# trill-ring.net
KiCad netlist of a schematic drawn in EAGLE
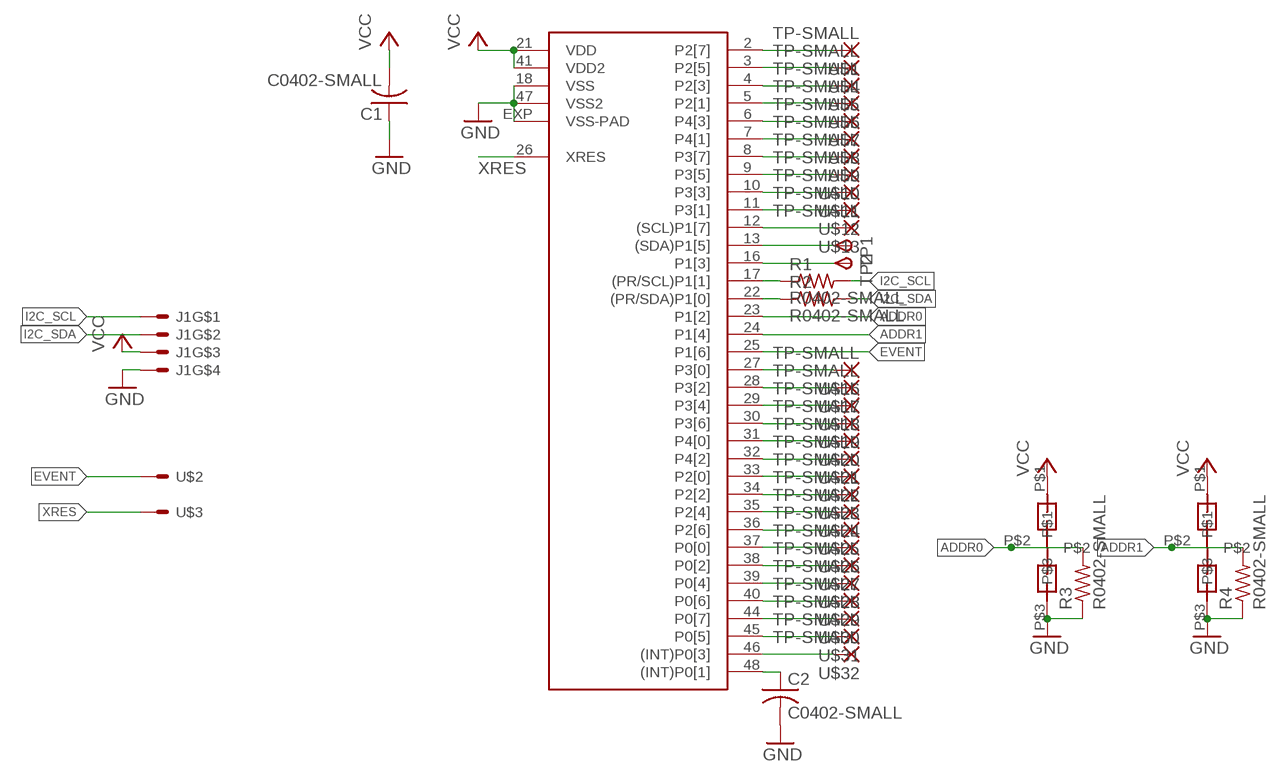
[diagram p0: schematic, sheet 1]

(export (version "E")
  (design (tool "Eeschema 10.0.6"))
  (components
    (comp (ref "C1")
      (value "C0402-SMALL")
      (footprint "eagle-import:C0402-SMALL")
      (libsource (lib "eagle-import") (part "C0402-SMALL"))
    )
    (comp (ref "C2")
      (value "C0402-SMALL")
      (footprint "eagle-import:C0402-SMALL")
      (libsource (lib "eagle-import") (part "C0402-SMALL"))
    )
    (comp (ref "IC1")
      (value "CY8C206X6A")
      (footprint "eagle-import:QFN48-LEADS")
      (libsource (lib "eagle-import") (part "CY8C206X6A"))
    )
    (comp (ref "J1")
      (value "GROVE-SMT")
      (footprint "eagle-import:JST-PH-4-SMT")
      (libsource (lib "eagle-import") (part "GROVE-SMT"))
    )
    (comp (ref "R1")
      (value "R0402-SMALL")
      (footprint "eagle-import:C0402-SMALL")
      (libsource (lib "eagle-import") (part "R0402-SMALL"))
    )
    (comp (ref "R2")
      (value "R0402-SMALL")
      (footprint "eagle-import:C0402-SMALL")
      (libsource (lib "eagle-import") (part "R0402-SMALL"))
    )
    (comp (ref "R3")
      (value "R0402-SMALL")
      (footprint "eagle-import:C0402-SMALL")
      (libsource (lib "eagle-import") (part "R0402-SMALL"))
    )
    (comp (ref "R4")
      (value "R0402-SMALL")
      (footprint "eagle-import:C0402-SMALL")
      (libsource (lib "eagle-import") (part "R0402-SMALL"))
    )
    (comp (ref "TP1")
      (value "TPSTP20R")
      (footprint "eagle-import:TP20R")
      (libsource (lib "eagle-import") (part "TPSTP20R"))
    )
    (comp (ref "TP2")
      (value "TPSTP20R")
      (footprint "eagle-import:TP20R")
      (libsource (lib "eagle-import") (part "TPSTP20R"))
    )
    (comp (ref "U$1")
      (value "TP-SMALL")
      (footprint "eagle-import:TESTPAD-SMALL")
      (libsource (lib "eagle-import") (part "TP-SMALL"))
    )
    (comp (ref "U$2")
      (value "JST-SMT-EXTRAPAD")
      (footprint "eagle-import:JST-SMT-EXTRAPAD")
      (libsource (lib "eagle-import") (part "JST-SMT-EXTRAPAD"))
    )
    (comp (ref "U$3")
      (value "JST-SMT-EXTRAPAD")
      (footprint "eagle-import:JST-SMT-EXTRAPAD")
      (libsource (lib "eagle-import") (part "JST-SMT-EXTRAPAD"))
    )
    (comp (ref "U$4")
      (value "TP-SMALL")
      (footprint "eagle-import:TESTPAD-SMALL")
      (libsource (lib "eagle-import") (part "TP-SMALL"))
    )
    (comp (ref "U$5")
      (value "TP-SMALL")
      (footprint "eagle-import:TESTPAD-SMALL")
      (libsource (lib "eagle-import") (part "TP-SMALL"))
    )
    (comp (ref "U$6")
      (value "TP-SMALL")
      (footprint "eagle-import:TESTPAD-SMALL")
      (libsource (lib "eagle-import") (part "TP-SMALL"))
    )
    (comp (ref "U$7")
      (value "TP-SMALL")
      (footprint "eagle-import:TESTPAD-SMALL")
      (libsource (lib "eagle-import") (part "TP-SMALL"))
    )
    (comp (ref "U$8")
      (value "TP-SMALL")
      (footprint "eagle-import:TESTPAD-SMALL")
      (libsource (lib "eagle-import") (part "TP-SMALL"))
    )
    (comp (ref "U$9")
      (value "TP-SMALL")
      (footprint "eagle-import:TESTPAD-SMALL")
      (libsource (lib "eagle-import") (part "TP-SMALL"))
    )
    (comp (ref "U$10")
      (value "TP-SMALL")
      (footprint "eagle-import:TESTPAD-SMALL")
      (libsource (lib "eagle-import") (part "TP-SMALL"))
    )
    (comp (ref "U$11")
      (value "TP-SMALL")
      (footprint "eagle-import:TESTPAD-SMALL")
      (libsource (lib "eagle-import") (part "TP-SMALL"))
    )
    (comp (ref "U$12")
      (value "TP-SMALL")
      (footprint "eagle-import:TESTPAD-SMALL")
      (libsource (lib "eagle-import") (part "TP-SMALL"))
    )
    (comp (ref "U$13")
      (value "TP-SMALL")
      (footprint "eagle-import:TESTPAD-SMALL")
      (libsource (lib "eagle-import") (part "TP-SMALL"))
    )
    (comp (ref "U$14")
      (value "SOLDER_JUMPER_3PAD")
      (footprint "eagle-import:SOLDER_JUMPER_3PAD")
      (libsource (lib "eagle-import") (part "SOLDER_JUMPER_3PAD"))
    )
    (comp (ref "U$15")
      (value "SOLDER_JUMPER_3PAD")
      (footprint "eagle-import:SOLDER_JUMPER_3PAD")
      (libsource (lib "eagle-import") (part "SOLDER_JUMPER_3PAD"))
    )
    (comp (ref "U$16")
      (value "TP-SMALL")
      (footprint "eagle-import:TESTPAD-SMALL")
      (libsource (lib "eagle-import") (part "TP-SMALL"))
    )
    (comp (ref "U$17")
      (value "TP-SMALL")
      (footprint "eagle-import:TESTPAD-SMALL")
      (libsource (lib "eagle-import") (part "TP-SMALL"))
    )
    (comp (ref "U$18")
      (value "TP-SMALL")
      (footprint "eagle-import:TESTPAD-SMALL")
      (libsource (lib "eagle-import") (part "TP-SMALL"))
    )
    (comp (ref "U$19")
      (value "TP-SMALL")
      (footprint "eagle-import:TESTPAD-SMALL")
      (libsource (lib "eagle-import") (part "TP-SMALL"))
    )
    (comp (ref "U$20")
      (value "TP-SMALL")
      (footprint "eagle-import:TESTPAD-SMALL")
      (libsource (lib "eagle-import") (part "TP-SMALL"))
    )
    (comp (ref "U$21")
      (value "TP-SMALL")
      (footprint "eagle-import:TESTPAD-SMALL")
      (libsource (lib "eagle-import") (part "TP-SMALL"))
    )
    (comp (ref "U$22")
      (value "TP-SMALL")
      (footprint "eagle-import:TESTPAD-SMALL")
      (libsource (lib "eagle-import") (part "TP-SMALL"))
    )
    (comp (ref "U$23")
      (value "TP-SMALL")
      (footprint "eagle-import:TESTPAD-SMALL")
      (libsource (lib "eagle-import") (part "TP-SMALL"))
    )
    (comp (ref "U$24")
      (value "TP-SMALL")
      (footprint "eagle-import:TESTPAD-SMALL")
      (libsource (lib "eagle-import") (part "TP-SMALL"))
    )
    (comp (ref "U$25")
      (value "TP-SMALL")
      (footprint "eagle-import:TESTPAD-SMALL")
      (libsource (lib "eagle-import") (part "TP-SMALL"))
    )
    (comp (ref "U$26")
      (value "TP-SMALL")
      (footprint "eagle-import:TESTPAD-SMALL")
      (libsource (lib "eagle-import") (part "TP-SMALL"))
    )
    (comp (ref "U$27")
      (value "TP-SMALL")
      (footprint "eagle-import:TESTPAD-SMALL")
      (libsource (lib "eagle-import") (part "TP-SMALL"))
    )
    (comp (ref "U$28")
      (value "TP-SMALL")
      (footprint "eagle-import:TESTPAD-SMALL")
      (libsource (lib "eagle-import") (part "TP-SMALL"))
    )
    (comp (ref "U$29")
      (value "TP-SMALL")
      (footprint "eagle-import:TESTPAD-SMALL")
      (libsource (lib "eagle-import") (part "TP-SMALL"))
    )
    (comp (ref "U$30")
      (value "TP-SMALL")
      (footprint "eagle-import:TESTPAD-SMALL")
      (libsource (lib "eagle-import") (part "TP-SMALL"))
    )
    (comp (ref "U$31")
      (value "TP-SMALL")
      (footprint "eagle-import:TESTPAD-SMALL")
      (libsource (lib "eagle-import") (part "TP-SMALL"))
    )
    (comp (ref "U$32")
      (value "TP-SMALL")
      (footprint "eagle-import:TESTPAD-SMALL")
      (libsource (lib "eagle-import") (part "TP-SMALL"))
    )
  )
  (nets
    (net (code "1") (name "ADDR0") (class "Default")
      (node (ref "IC1") (pin "23") (pinfunction "P1[2]_23") (pintype "bidirectional"))
      (node (ref "R3") (pin "P$2") (pinfunction "2_P$2") (pintype "passive"))
      (node (ref "U$14") (pin "P$2") (pinfunction "P$2_P$2") (pintype "bidirectional"))
    )
    (net (code "2") (name "ADDR1") (class "Default")
      (node (ref "IC1") (pin "24") (pinfunction "P1[4]_24") (pintype "bidirectional"))
      (node (ref "R4") (pin "P$2") (pinfunction "2_P$2") (pintype "passive"))
      (node (ref "U$15") (pin "P$2") (pinfunction "P$2_P$2") (pintype "bidirectional"))
    )
    (net (code "3") (name "EVENT") (class "Default")
      (node (ref "IC1") (pin "25") (pinfunction "P1[6]_25") (pintype "bidirectional"))
      (node (ref "U$2") (pin "P$1") (pinfunction "S_P$1") (pintype "passive"))
    )
    (net (code "4") (name "GND") (class "Default")
      (node (ref "C1") (pin "P$1") (pinfunction "1_P$1") (pintype "passive"))
      (node (ref "C2") (pin "P$2") (pinfunction "2_P$2") (pintype "passive"))
      (node (ref "IC1") (pin "18") (pinfunction "VSS_18") (pintype "bidirectional"))
      (node (ref "IC1") (pin "47") (pinfunction "VSS2_47") (pintype "bidirectional"))
      (node (ref "IC1") (pin "EXP") (pinfunction "VSS-PAD_EXP") (pintype "bidirectional"))
      (node (ref "J1") (pin "4") (pinfunction "S_4") (pintype "passive"))
      (node (ref "R3") (pin "P$1") (pinfunction "1_P$1") (pintype "passive"))
      (node (ref "R4") (pin "P$1") (pinfunction "1_P$1") (pintype "passive"))
      (node (ref "U$14") (pin "P$3") (pinfunction "P$3_P$3") (pintype "bidirectional"))
      (node (ref "U$15") (pin "P$3") (pinfunction "P$3_P$3") (pintype "bidirectional"))
    )
    (net (code "5") (name "I2C_SCL") (class "Default")
      (node (ref "J1") (pin "1") (pinfunction "S_1") (pintype "passive"))
      (node (ref "R1") (pin "P$2") (pinfunction "2_P$2") (pintype "passive"))
    )
    (net (code "6") (name "I2C_SDA") (class "Default")
      (node (ref "J1") (pin "2") (pinfunction "S_2") (pintype "passive"))
      (node (ref "R2") (pin "P$2") (pinfunction "2_P$2") (pintype "passive"))
    )
    (net (code "7") (name "Net-(C2-1)") (class "Default")
      (node (ref "C2") (pin "P$1") (pinfunction "1_P$1") (pintype "passive"))
      (node (ref "IC1") (pin "48") (pinfunction "(INT)P0[1]_48") (pintype "bidirectional"))
    )
    (net (code "8") (name "Net-(IC1-(INT)P0[3])") (class "Default")
      (node (ref "IC1") (pin "46") (pinfunction "(INT)P0[3]_46") (pintype "bidirectional"))
      (node (ref "U$32") (pin "P$1") (pinfunction "P_P$1") (pintype "passive"))
    )
    (net (code "9") (name "Net-(IC1-(PR{slash}SCL)P1[1])") (class "Default")
      (node (ref "IC1") (pin "17") (pinfunction "(PR/SCL)P1[1]_17") (pintype "bidirectional"))
      (node (ref "R1") (pin "P$1") (pinfunction "1_P$1") (pintype "passive"))
    )
    (net (code "10") (name "Net-(IC1-(PR{slash}SDA)P1[0])") (class "Default")
      (node (ref "IC1") (pin "22") (pinfunction "(PR/SDA)P1[0]_22") (pintype "bidirectional"))
      (node (ref "R2") (pin "P$1") (pinfunction "1_P$1") (pintype "passive"))
    )
    (net (code "11") (name "Net-(IC1-(SCL)P1[7])") (class "Default")
      (node (ref "IC1") (pin "12") (pinfunction "(SCL)P1[7]_12") (pintype "bidirectional"))
      (node (ref "U$13") (pin "P$1") (pinfunction "P_P$1") (pintype "passive"))
    )
    (net (code "12") (name "Net-(IC1-(SDA)P1[5])") (class "Default")
      (node (ref "IC1") (pin "13") (pinfunction "(SDA)P1[5]_13") (pintype "bidirectional"))
      (node (ref "TP1") (pin "TP") (pinfunction "PP_TP") (pintype "input"))
    )
    (net (code "13") (name "Net-(IC1-P0[0])") (class "Default")
      (node (ref "IC1") (pin "37") (pinfunction "P0[0]_37") (pintype "bidirectional"))
      (node (ref "U$26") (pin "P$1") (pinfunction "P_P$1") (pintype "passive"))
    )
    (net (code "14") (name "Net-(IC1-P0[2])") (class "Default")
      (node (ref "IC1") (pin "38") (pinfunction "P0[2]_38") (pintype "bidirectional"))
      (node (ref "U$27") (pin "P$1") (pinfunction "P_P$1") (pintype "passive"))
    )
    (net (code "15") (name "Net-(IC1-P0[4])") (class "Default")
      (node (ref "IC1") (pin "39") (pinfunction "P0[4]_39") (pintype "bidirectional"))
      (node (ref "U$28") (pin "P$1") (pinfunction "P_P$1") (pintype "passive"))
    )
    (net (code "16") (name "Net-(IC1-P0[5])") (class "Default")
      (node (ref "IC1") (pin "45") (pinfunction "P0[5]_45") (pintype "bidirectional"))
      (node (ref "U$31") (pin "P$1") (pinfunction "P_P$1") (pintype "passive"))
    )
    (net (code "17") (name "Net-(IC1-P0[6])") (class "Default")
      (node (ref "IC1") (pin "40") (pinfunction "P0[6]_40") (pintype "bidirectional"))
      (node (ref "U$29") (pin "P$1") (pinfunction "P_P$1") (pintype "passive"))
    )
    (net (code "18") (name "Net-(IC1-P0[7])") (class "Default")
      (node (ref "IC1") (pin "44") (pinfunction "P0[7]_44") (pintype "bidirectional"))
      (node (ref "U$30") (pin "P$1") (pinfunction "P_P$1") (pintype "passive"))
    )
    (net (code "19") (name "Net-(IC1-P1[3])") (class "Default")
      (node (ref "IC1") (pin "16") (pinfunction "P1[3]_16") (pintype "bidirectional"))
      (node (ref "TP2") (pin "TP") (pinfunction "PP_TP") (pintype "input"))
    )
    (net (code "20") (name "Net-(IC1-P2[0])") (class "Default")
      (node (ref "IC1") (pin "33") (pinfunction "P2[0]_33") (pintype "bidirectional"))
      (node (ref "U$22") (pin "P$1") (pinfunction "P_P$1") (pintype "passive"))
    )
    (net (code "21") (name "Net-(IC1-P2[1])") (class "Default")
      (node (ref "IC1") (pin "5") (pinfunction "P2[1]_5") (pintype "bidirectional"))
      (node (ref "U$6") (pin "P$1") (pinfunction "P_P$1") (pintype "passive"))
    )
    (net (code "22") (name "Net-(IC1-P2[2])") (class "Default")
      (node (ref "IC1") (pin "34") (pinfunction "P2[2]_34") (pintype "bidirectional"))
      (node (ref "U$23") (pin "P$1") (pinfunction "P_P$1") (pintype "passive"))
    )
    (net (code "23") (name "Net-(IC1-P2[3])") (class "Default")
      (node (ref "IC1") (pin "4") (pinfunction "P2[3]_4") (pintype "bidirectional"))
      (node (ref "U$5") (pin "P$1") (pinfunction "P_P$1") (pintype "passive"))
    )
    (net (code "24") (name "Net-(IC1-P2[4])") (class "Default")
      (node (ref "IC1") (pin "35") (pinfunction "P2[4]_35") (pintype "bidirectional"))
      (node (ref "U$24") (pin "P$1") (pinfunction "P_P$1") (pintype "passive"))
    )
    (net (code "25") (name "Net-(IC1-P2[5])") (class "Default")
      (node (ref "IC1") (pin "3") (pinfunction "P2[5]_3") (pintype "bidirectional"))
      (node (ref "U$4") (pin "P$1") (pinfunction "P_P$1") (pintype "passive"))
    )
    (net (code "26") (name "Net-(IC1-P2[6])") (class "Default")
      (node (ref "IC1") (pin "36") (pinfunction "P2[6]_36") (pintype "bidirectional"))
      (node (ref "U$25") (pin "P$1") (pinfunction "P_P$1") (pintype "passive"))
    )
    (net (code "27") (name "Net-(IC1-P2[7])") (class "Default")
      (node (ref "IC1") (pin "2") (pinfunction "P2[7]_2") (pintype "bidirectional"))
      (node (ref "U$1") (pin "P$1") (pinfunction "P_P$1") (pintype "passive"))
    )
    (net (code "28") (name "Net-(IC1-P3[0])") (class "Default")
      (node (ref "IC1") (pin "27") (pinfunction "P3[0]_27") (pintype "bidirectional"))
      (node (ref "U$16") (pin "P$1") (pinfunction "P_P$1") (pintype "passive"))
    )
    (net (code "29") (name "Net-(IC1-P3[1])") (class "Default")
      (node (ref "IC1") (pin "11") (pinfunction "P3[1]_11") (pintype "bidirectional"))
      (node (ref "U$12") (pin "P$1") (pinfunction "P_P$1") (pintype "passive"))
    )
    (net (code "30") (name "Net-(IC1-P3[2])") (class "Default")
      (node (ref "IC1") (pin "28") (pinfunction "P3[2]_28") (pintype "bidirectional"))
      (node (ref "U$17") (pin "P$1") (pinfunction "P_P$1") (pintype "passive"))
    )
    (net (code "31") (name "Net-(IC1-P3[3])") (class "Default")
      (node (ref "IC1") (pin "10") (pinfunction "P3[3]_10") (pintype "bidirectional"))
      (node (ref "U$11") (pin "P$1") (pinfunction "P_P$1") (pintype "passive"))
    )
    (net (code "32") (name "Net-(IC1-P3[4])") (class "Default")
      (node (ref "IC1") (pin "29") (pinfunction "P3[4]_29") (pintype "bidirectional"))
      (node (ref "U$18") (pin "P$1") (pinfunction "P_P$1") (pintype "passive"))
    )
    (net (code "33") (name "Net-(IC1-P3[5])") (class "Default")
      (node (ref "IC1") (pin "9") (pinfunction "P3[5]_9") (pintype "bidirectional"))
      (node (ref "U$10") (pin "P$1") (pinfunction "P_P$1") (pintype "passive"))
    )
    (net (code "34") (name "Net-(IC1-P3[6])") (class "Default")
      (node (ref "IC1") (pin "30") (pinfunction "P3[6]_30") (pintype "bidirectional"))
      (node (ref "U$19") (pin "P$1") (pinfunction "P_P$1") (pintype "passive"))
    )
    (net (code "35") (name "Net-(IC1-P3[7])") (class "Default")
      (node (ref "IC1") (pin "8") (pinfunction "P3[7]_8") (pintype "bidirectional"))
      (node (ref "U$9") (pin "P$1") (pinfunction "P_P$1") (pintype "passive"))
    )
    (net (code "36") (name "Net-(IC1-P4[0])") (class "Default")
      (node (ref "IC1") (pin "31") (pinfunction "P4[0]_31") (pintype "bidirectional"))
      (node (ref "U$20") (pin "P$1") (pinfunction "P_P$1") (pintype "passive"))
    )
    (net (code "37") (name "Net-(IC1-P4[1])") (class "Default")
      (node (ref "IC1") (pin "7") (pinfunction "P4[1]_7") (pintype "bidirectional"))
      (node (ref "U$8") (pin "P$1") (pinfunction "P_P$1") (pintype "passive"))
    )
    (net (code "38") (name "Net-(IC1-P4[2])") (class "Default")
      (node (ref "IC1") (pin "32") (pinfunction "P4[2]_32") (pintype "bidirectional"))
      (node (ref "U$21") (pin "P$1") (pinfunction "P_P$1") (pintype "passive"))
    )
    (net (code "39") (name "Net-(IC1-P4[3])") (class "Default")
      (node (ref "IC1") (pin "6") (pinfunction "P4[3]_6") (pintype "bidirectional"))
      (node (ref "U$7") (pin "P$1") (pinfunction "P_P$1") (pintype "passive"))
    )
    (net (code "40") (name "VCC") (class "Default")
      (node (ref "C1") (pin "P$2") (pinfunction "2_P$2") (pintype "passive"))
      (node (ref "IC1") (pin "21") (pinfunction "VDD_21") (pintype "bidirectional"))
      (node (ref "IC1") (pin "41") (pinfunction "VDD2_41") (pintype "bidirectional"))
      (node (ref "J1") (pin "3") (pinfunction "S_3") (pintype "passive"))
      (node (ref "U$14") (pin "P$1") (pinfunction "P$1_P$1") (pintype "bidirectional"))
      (node (ref "U$15") (pin "P$1") (pinfunction "P$1_P$1") (pintype "bidirectional"))
    )
    (net (code "41") (name "XRES") (class "Default")
      (node (ref "IC1") (pin "26") (pinfunction "XRES_26") (pintype "bidirectional"))
      (node (ref "U$3") (pin "P$1") (pinfunction "S_P$1") (pintype "passive"))
    )
  )
)
